# Hub.net
KiCad netlist of a schematic drawn in EAGLE
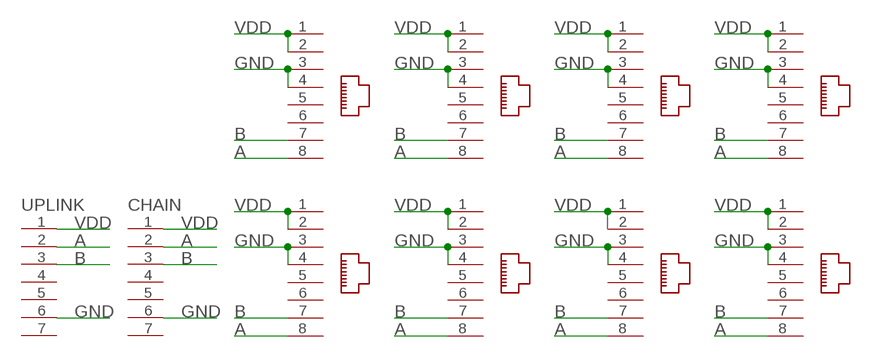
[diagram p0: schematic, sheet 1]

(export (version "E")
  (design (tool "Eeschema 10.0.6"))
  (components
    (comp (ref "1")
      (value "RJ45-8P8C")
      (footprint "eagle-import:RJ45-8P8C")
      (libsource (lib "eagle-import") (part "RJ45-8P8C"))
    )
    (comp (ref "2")
      (value "RJ45-8P8C")
      (footprint "eagle-import:RJ45-8P8C")
      (libsource (lib "eagle-import") (part "RJ45-8P8C"))
    )
    (comp (ref "3")
      (value "RJ45-8P8C")
      (footprint "eagle-import:RJ45-8P8C")
      (libsource (lib "eagle-import") (part "RJ45-8P8C"))
    )
    (comp (ref "4")
      (value "RJ45-8P8C")
      (footprint "eagle-import:RJ45-8P8C")
      (libsource (lib "eagle-import") (part "RJ45-8P8C"))
    )
    (comp (ref "5")
      (value "RJ45-8P8C")
      (footprint "eagle-import:RJ45-8P8C")
      (libsource (lib "eagle-import") (part "RJ45-8P8C"))
    )
    (comp (ref "6")
      (value "RJ45-8P8C")
      (footprint "eagle-import:RJ45-8P8C")
      (libsource (lib "eagle-import") (part "RJ45-8P8C"))
    )
    (comp (ref "7")
      (value "RJ45-8P8C")
      (footprint "eagle-import:RJ45-8P8C")
      (libsource (lib "eagle-import") (part "RJ45-8P8C"))
    )
    (comp (ref "8")
      (value "RJ45-8P8C")
      (footprint "eagle-import:RJ45-8P8C")
      (libsource (lib "eagle-import") (part "RJ45-8P8C"))
    )
    (comp (ref "CHAIN")
      (value "GX12-7P")
      (footprint "eagle-import:GX12-7P")
      (libsource (lib "eagle-import") (part "GX12-7P"))
    )
    (comp (ref "UPLINK")
      (value "GX12-7P")
      (footprint "eagle-import:GX12-7P")
      (libsource (lib "eagle-import") (part "GX12-7P"))
    )
  )
  (nets
    (net (code "1") (name "/A") (class "Default")
      (node (ref "1") (pin "8") (pinfunction "8_8") (pintype "bidirectional"))
      (node (ref "2") (pin "8") (pinfunction "8_8") (pintype "bidirectional"))
      (node (ref "3") (pin "8") (pinfunction "8_8") (pintype "bidirectional"))
      (node (ref "4") (pin "8") (pinfunction "8_8") (pintype "bidirectional"))
      (node (ref "5") (pin "8") (pinfunction "8_8") (pintype "bidirectional"))
      (node (ref "6") (pin "8") (pinfunction "8_8") (pintype "bidirectional"))
      (node (ref "7") (pin "8") (pinfunction "8_8") (pintype "bidirectional"))
      (node (ref "8") (pin "8") (pinfunction "8_8") (pintype "bidirectional"))
      (node (ref "CHAIN") (pin "2") (pinfunction "2_2") (pintype "bidirectional"))
      (node (ref "UPLINK") (pin "2") (pinfunction "2_2") (pintype "bidirectional"))
    )
    (net (code "2") (name "/B") (class "Default")
      (node (ref "1") (pin "7") (pinfunction "7_7") (pintype "bidirectional"))
      (node (ref "2") (pin "7") (pinfunction "7_7") (pintype "bidirectional"))
      (node (ref "3") (pin "7") (pinfunction "7_7") (pintype "bidirectional"))
      (node (ref "4") (pin "7") (pinfunction "7_7") (pintype "bidirectional"))
      (node (ref "5") (pin "7") (pinfunction "7_7") (pintype "bidirectional"))
      (node (ref "6") (pin "7") (pinfunction "7_7") (pintype "bidirectional"))
      (node (ref "7") (pin "7") (pinfunction "7_7") (pintype "bidirectional"))
      (node (ref "8") (pin "7") (pinfunction "7_7") (pintype "bidirectional"))
      (node (ref "CHAIN") (pin "3") (pinfunction "3_3") (pintype "bidirectional"))
      (node (ref "UPLINK") (pin "3") (pinfunction "3_3") (pintype "bidirectional"))
    )
    (net (code "3") (name "/GND") (class "Default")
      (node (ref "1") (pin "3") (pinfunction "3_3") (pintype "bidirectional"))
      (node (ref "1") (pin "4") (pinfunction "4_4") (pintype "bidirectional"))
      (node (ref "2") (pin "3") (pinfunction "3_3") (pintype "bidirectional"))
      (node (ref "2") (pin "4") (pinfunction "4_4") (pintype "bidirectional"))
      (node (ref "3") (pin "3") (pinfunction "3_3") (pintype "bidirectional"))
      (node (ref "3") (pin "4") (pinfunction "4_4") (pintype "bidirectional"))
      (node (ref "4") (pin "3") (pinfunction "3_3") (pintype "bidirectional"))
      (node (ref "4") (pin "4") (pinfunction "4_4") (pintype "bidirectional"))
      (node (ref "5") (pin "3") (pinfunction "3_3") (pintype "bidirectional"))
      (node (ref "5") (pin "4") (pinfunction "4_4") (pintype "bidirectional"))
      (node (ref "6") (pin "3") (pinfunction "3_3") (pintype "bidirectional"))
      (node (ref "6") (pin "4") (pinfunction "4_4") (pintype "bidirectional"))
      (node (ref "7") (pin "3") (pinfunction "3_3") (pintype "bidirectional"))
      (node (ref "7") (pin "4") (pinfunction "4_4") (pintype "bidirectional"))
      (node (ref "8") (pin "3") (pinfunction "3_3") (pintype "bidirectional"))
      (node (ref "8") (pin "4") (pinfunction "4_4") (pintype "bidirectional"))
      (node (ref "CHAIN") (pin "6") (pinfunction "6_6") (pintype "bidirectional"))
      (node (ref "UPLINK") (pin "6") (pinfunction "6_6") (pintype "bidirectional"))
    )
    (net (code "4") (name "/VDD") (class "Default")
      (node (ref "1") (pin "1") (pinfunction "1_1") (pintype "bidirectional"))
      (node (ref "1") (pin "2") (pinfunction "2_2") (pintype "bidirectional"))
      (node (ref "2") (pin "1") (pinfunction "1_1") (pintype "bidirectional"))
      (node (ref "2") (pin "2") (pinfunction "2_2") (pintype "bidirectional"))
      (node (ref "3") (pin "1") (pinfunction "1_1") (pintype "bidirectional"))
      (node (ref "3") (pin "2") (pinfunction "2_2") (pintype "bidirectional"))
      (node (ref "4") (pin "1") (pinfunction "1_1") (pintype "bidirectional"))
      (node (ref "4") (pin "2") (pinfunction "2_2") (pintype "bidirectional"))
      (node (ref "5") (pin "1") (pinfunction "1_1") (pintype "bidirectional"))
      (node (ref "5") (pin "2") (pinfunction "2_2") (pintype "bidirectional"))
      (node (ref "6") (pin "1") (pinfunction "1_1") (pintype "bidirectional"))
      (node (ref "6") (pin "2") (pinfunction "2_2") (pintype "bidirectional"))
      (node (ref "7") (pin "1") (pinfunction "1_1") (pintype "bidirectional"))
      (node (ref "7") (pin "2") (pinfunction "2_2") (pintype "bidirectional"))
      (node (ref "8") (pin "1") (pinfunction "1_1") (pintype "bidirectional"))
      (node (ref "8") (pin "2") (pinfunction "2_2") (pintype "bidirectional"))
      (node (ref "CHAIN") (pin "1") (pinfunction "1_1") (pintype "bidirectional"))
      (node (ref "UPLINK") (pin "1") (pinfunction "1_1") (pintype "bidirectional"))
    )
    (net (code "5") (name "unconnected-(1-Pad5)") (class "Default")
      (node (ref "1") (pin "5") (pinfunction "5_5") (pintype "bidirectional"))
    )
    (net (code "6") (name "unconnected-(1-Pad6)") (class "Default")
      (node (ref "1") (pin "6") (pinfunction "6_6") (pintype "bidirectional"))
    )
    (net (code "7") (name "unconnected-(2-Pad5)") (class "Default")
      (node (ref "2") (pin "5") (pinfunction "5_5") (pintype "bidirectional"))
    )
    (net (code "8") (name "unconnected-(2-Pad6)") (class "Default")
      (node (ref "2") (pin "6") (pinfunction "6_6") (pintype "bidirectional"))
    )
    (net (code "9") (name "unconnected-(3-Pad5)") (class "Default")
      (node (ref "3") (pin "5") (pinfunction "5_5") (pintype "bidirectional"))
    )
    (net (code "10") (name "unconnected-(3-Pad6)") (class "Default")
      (node (ref "3") (pin "6") (pinfunction "6_6") (pintype "bidirectional"))
    )
    (net (code "11") (name "unconnected-(4-Pad5)") (class "Default")
      (node (ref "4") (pin "5") (pinfunction "5_5") (pintype "bidirectional"))
    )
    (net (code "12") (name "unconnected-(4-Pad6)") (class "Default")
      (node (ref "4") (pin "6") (pinfunction "6_6") (pintype "bidirectional"))
    )
    (net (code "13") (name "unconnected-(5-Pad5)") (class "Default")
      (node (ref "5") (pin "5") (pinfunction "5_5") (pintype "bidirectional"))
    )
    (net (code "14") (name "unconnected-(5-Pad6)") (class "Default")
      (node (ref "5") (pin "6") (pinfunction "6_6") (pintype "bidirectional"))
    )
    (net (code "15") (name "unconnected-(6-Pad5)") (class "Default")
      (node (ref "6") (pin "5") (pinfunction "5_5") (pintype "bidirectional"))
    )
    (net (code "16") (name "unconnected-(6-Pad6)") (class "Default")
      (node (ref "6") (pin "6") (pinfunction "6_6") (pintype "bidirectional"))
    )
    (net (code "17") (name "unconnected-(7-Pad5)") (class "Default")
      (node (ref "7") (pin "5") (pinfunction "5_5") (pintype "bidirectional"))
    )
    (net (code "18") (name "unconnected-(7-Pad6)") (class "Default")
      (node (ref "7") (pin "6") (pinfunction "6_6") (pintype "bidirectional"))
    )
    (net (code "19") (name "unconnected-(8-Pad5)") (class "Default")
      (node (ref "8") (pin "5") (pinfunction "5_5") (pintype "bidirectional"))
    )
    (net (code "20") (name "unconnected-(8-Pad6)") (class "Default")
      (node (ref "8") (pin "6") (pinfunction "6_6") (pintype "bidirectional"))
    )
    (net (code "21") (name "unconnected-(CHAIN-Pad4)") (class "Default")
      (node (ref "CHAIN") (pin "4") (pinfunction "4_4") (pintype "bidirectional"))
    )
    (net (code "22") (name "unconnected-(CHAIN-Pad5)") (class "Default")
      (node (ref "CHAIN") (pin "5") (pinfunction "5_5") (pintype "bidirectional"))
    )
    (net (code "23") (name "unconnected-(CHAIN-Pad7)") (class "Default")
      (node (ref "CHAIN") (pin "7") (pinfunction "7_7") (pintype "bidirectional"))
    )
    (net (code "24") (name "unconnected-(UPLINK-Pad4)") (class "Default")
      (node (ref "UPLINK") (pin "4") (pinfunction "4_4") (pintype "bidirectional"))
    )
    (net (code "25") (name "unconnected-(UPLINK-Pad5)") (class "Default")
      (node (ref "UPLINK") (pin "5") (pinfunction "5_5") (pintype "bidirectional"))
    )
    (net (code "26") (name "unconnected-(UPLINK-Pad7)") (class "Default")
      (node (ref "UPLINK") (pin "7") (pinfunction "7_7") (pintype "bidirectional"))
    )
  )
)
